# Design.net
KiCad netlist of a schematic drawn in EAGLE
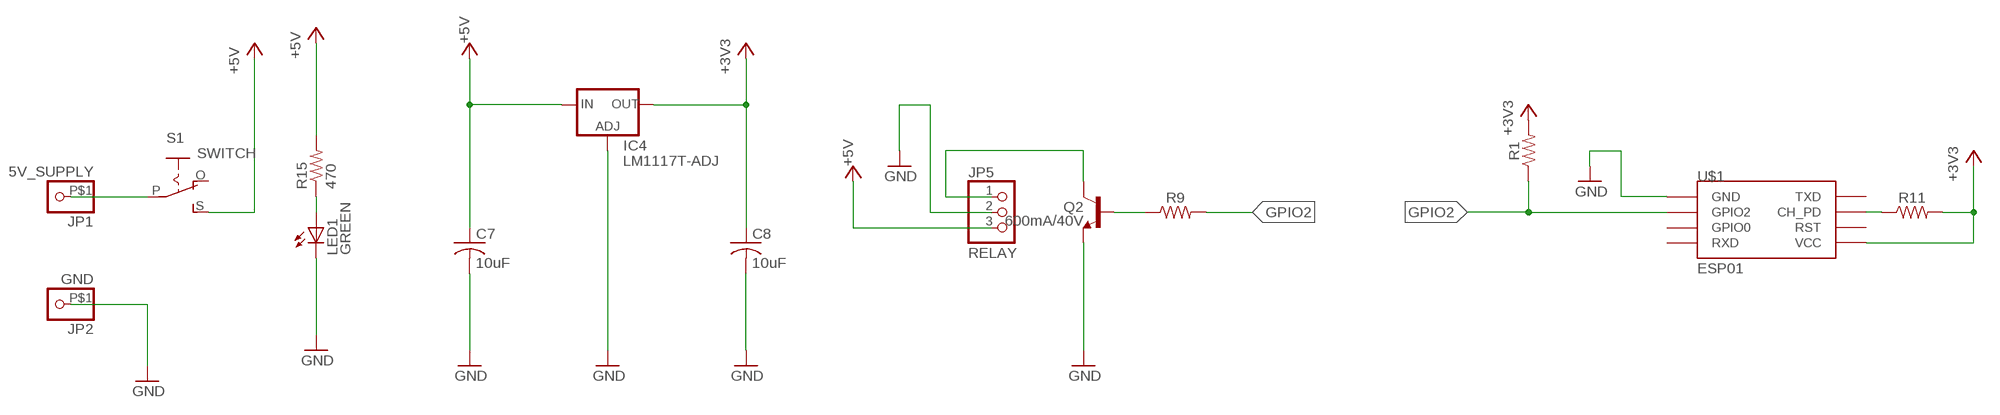
[diagram p0: schematic, sheet 1]

(export (version "E")
  (design (tool "Eeschema 10.0.6"))
  (components
    (comp (ref "C7")
      (value "10uF")
      (footprint "eagle-import:C025-025X050")
      (libsource (lib "eagle-import") (part "C-US025-025X050"))
    )
    (comp (ref "C8")
      (value "10uF")
      (footprint "eagle-import:C025-025X050")
      (libsource (lib "eagle-import") (part "C-US025-025X050"))
    )
    (comp (ref "IC4")
      (value "LM1117T-ADJ")
      (footprint "eagle-import:TO220")
      (libsource (lib "eagle-import") (part "LM1117T-ADJ"))
    )
    (comp (ref "JP1")
      (value "5V_SUPPLY")
      (footprint "eagle-import:1X1-BIGPOGO")
      (libsource (lib "eagle-import") (part "PINHD-1X1-BIGPOGO"))
    )
    (comp (ref "JP2")
      (value "GND")
      (footprint "eagle-import:1X1-BIGPOGO")
      (libsource (lib "eagle-import") (part "PINHD-1X1-BIGPOGO"))
    )
    (comp (ref "JP5")
      (value "RELAY")
      (footprint "eagle-import:1X03")
      (libsource (lib "eagle-import") (part "PINHD-1X3"))
    )
    (comp (ref "LED1")
      (value "GREEN")
      (footprint "eagle-import:LED5MM")
      (libsource (lib "eagle-import") (part "LED5MM"))
    )
    (comp (ref "Q2")
      (value "600mA/40V")
      (footprint "eagle-import:TO-92")
      (libsource (lib "eagle-import") (part "TRANS_NPN-P2N2222A"))
    )
    (comp (ref "R1")
      (value "10k")
      (footprint "eagle-import:0207_12")
      (libsource (lib "eagle-import") (part "R-US_0207/12"))
    )
    (comp (ref "R9")
      (value "4.7k")
      (footprint "eagle-import:0207_12")
      (libsource (lib "eagle-import") (part "R-US_0207/12"))
    )
    (comp (ref "R11")
      (value "10k")
      (footprint "eagle-import:0207_12")
      (libsource (lib "eagle-import") (part "R-US_0207/12"))
    )
    (comp (ref "R15")
      (value "470")
      (footprint "eagle-import:0207_12")
      (libsource (lib "eagle-import") (part "R-US_0207/12"))
    )
    (comp (ref "S1")
      (value "SWITCH")
      (footprint "eagle-import:EG1218")
      (libsource (lib "eagle-import") (part "EG1218S"))
    )
    (comp (ref "U$1")
      (value "ESP01")
      (footprint "eagle-import:ESP01")
      (libsource (lib "eagle-import") (part "ESP01"))
    )
  )
  (nets
    (net (code "1") (name "+3V3") (class "Default")
      (node (ref "C8") (pin "1") (pinfunction "1_1") (pintype "passive"))
      (node (ref "IC4") (pin "2") (pinfunction "OUT_2") (pintype "passive"))
      (node (ref "R1") (pin "2") (pinfunction "2_2") (pintype "passive"))
      (node (ref "R11") (pin "2") (pinfunction "2_2") (pintype "passive"))
      (node (ref "U$1") (pin "VCC") (pinfunction "VCC_VCC") (pintype "bidirectional"))
    )
    (net (code "2") (name "+5V") (class "Default")
      (node (ref "C7") (pin "1") (pinfunction "1_1") (pintype "passive"))
      (node (ref "IC4") (pin "3") (pinfunction "IN_3") (pintype "input"))
      (node (ref "JP5") (pin "3") (pinfunction "3_3") (pintype "passive"))
      (node (ref "R15") (pin "2") (pinfunction "2_2") (pintype "passive"))
      (node (ref "S1") (pin "S") (pinfunction "S_S") (pintype "passive"))
    )
    (net (code "3") (name "GND") (class "Default")
      (node (ref "C7") (pin "2") (pinfunction "2_2") (pintype "passive"))
      (node (ref "C8") (pin "2") (pinfunction "2_2") (pintype "passive"))
      (node (ref "IC4") (pin "1") (pinfunction "ADJ_1") (pintype "input"))
      (node (ref "JP2") (pin "P$1") (pinfunction "1_P$1") (pintype "passive"))
      (node (ref "JP5") (pin "2") (pinfunction "2_2") (pintype "passive"))
      (node (ref "LED1") (pin "K") (pinfunction "C_K") (pintype "passive"))
      (node (ref "Q2") (pin "3") (pinfunction "E_3") (pintype "passive"))
      (node (ref "U$1") (pin "GND") (pinfunction "GND_GND") (pintype "bidirectional"))
    )
    (net (code "4") (name "GPIO2") (class "Default")
      (node (ref "R1") (pin "1") (pinfunction "1_1") (pintype "passive"))
      (node (ref "R9") (pin "2") (pinfunction "2_2") (pintype "passive"))
      (node (ref "U$1") (pin "GPIO2") (pinfunction "GPIO2_GPIO2") (pintype "bidirectional"))
    )
    (net (code "5") (name "Net-(JP1-1)") (class "Default")
      (node (ref "JP1") (pin "P$1") (pinfunction "1_P$1") (pintype "passive"))
      (node (ref "S1") (pin "P") (pinfunction "P_P") (pintype "passive"))
    )
    (net (code "6") (name "Net-(LED1-PadA)") (class "Default")
      (node (ref "LED1") (pin "A") (pinfunction "A_A") (pintype "passive"))
      (node (ref "R15") (pin "1") (pinfunction "1_1") (pintype "passive"))
    )
    (net (code "7") (name "Net-(Q2-B)") (class "Default")
      (node (ref "Q2") (pin "2") (pinfunction "B_2") (pintype "passive"))
      (node (ref "R9") (pin "1") (pinfunction "1_1") (pintype "passive"))
    )
    (net (code "8") (name "Net-(Q2-C)") (class "Default")
      (node (ref "JP5") (pin "1") (pinfunction "1_1") (pintype "passive"))
      (node (ref "Q2") (pin "1") (pinfunction "C_1") (pintype "passive"))
    )
    (net (code "9") (name "Net-(R11-Pad1)") (class "Default")
      (node (ref "R11") (pin "1") (pinfunction "1_1") (pintype "passive"))
      (node (ref "U$1") (pin "CH_PD") (pinfunction "CH_PD_CH_PD") (pintype "bidirectional"))
    )
    (net (code "10") (name "unconnected-(S1-PadO)") (class "Default")
      (node (ref "S1") (pin "O") (pinfunction "O_O") (pintype "passive"))
    )
    (net (code "11") (name "unconnected-(U$1-PadGPIO0)") (class "Default")
      (node (ref "U$1") (pin "GPIO0") (pinfunction "GPIO0_GPIO0") (pintype "bidirectional"))
    )
    (net (code "12") (name "unconnected-(U$1-PadRST)") (class "Default")
      (node (ref "U$1") (pin "RST") (pinfunction "RST_RST") (pintype "bidirectional"))
    )
    (net (code "13") (name "unconnected-(U$1-RXD-PadRX)") (class "Default")
      (node (ref "U$1") (pin "RX") (pinfunction "RXD_RX") (pintype "bidirectional"))
    )
    (net (code "14") (name "unconnected-(U$1-TXD-PadTX)") (class "Default")
      (node (ref "U$1") (pin "TX") (pinfunction "TXD_TX") (pintype "bidirectional"))
    )
  )
)
